# working.net
KiCad netlist of a schematic drawn in EAGLE
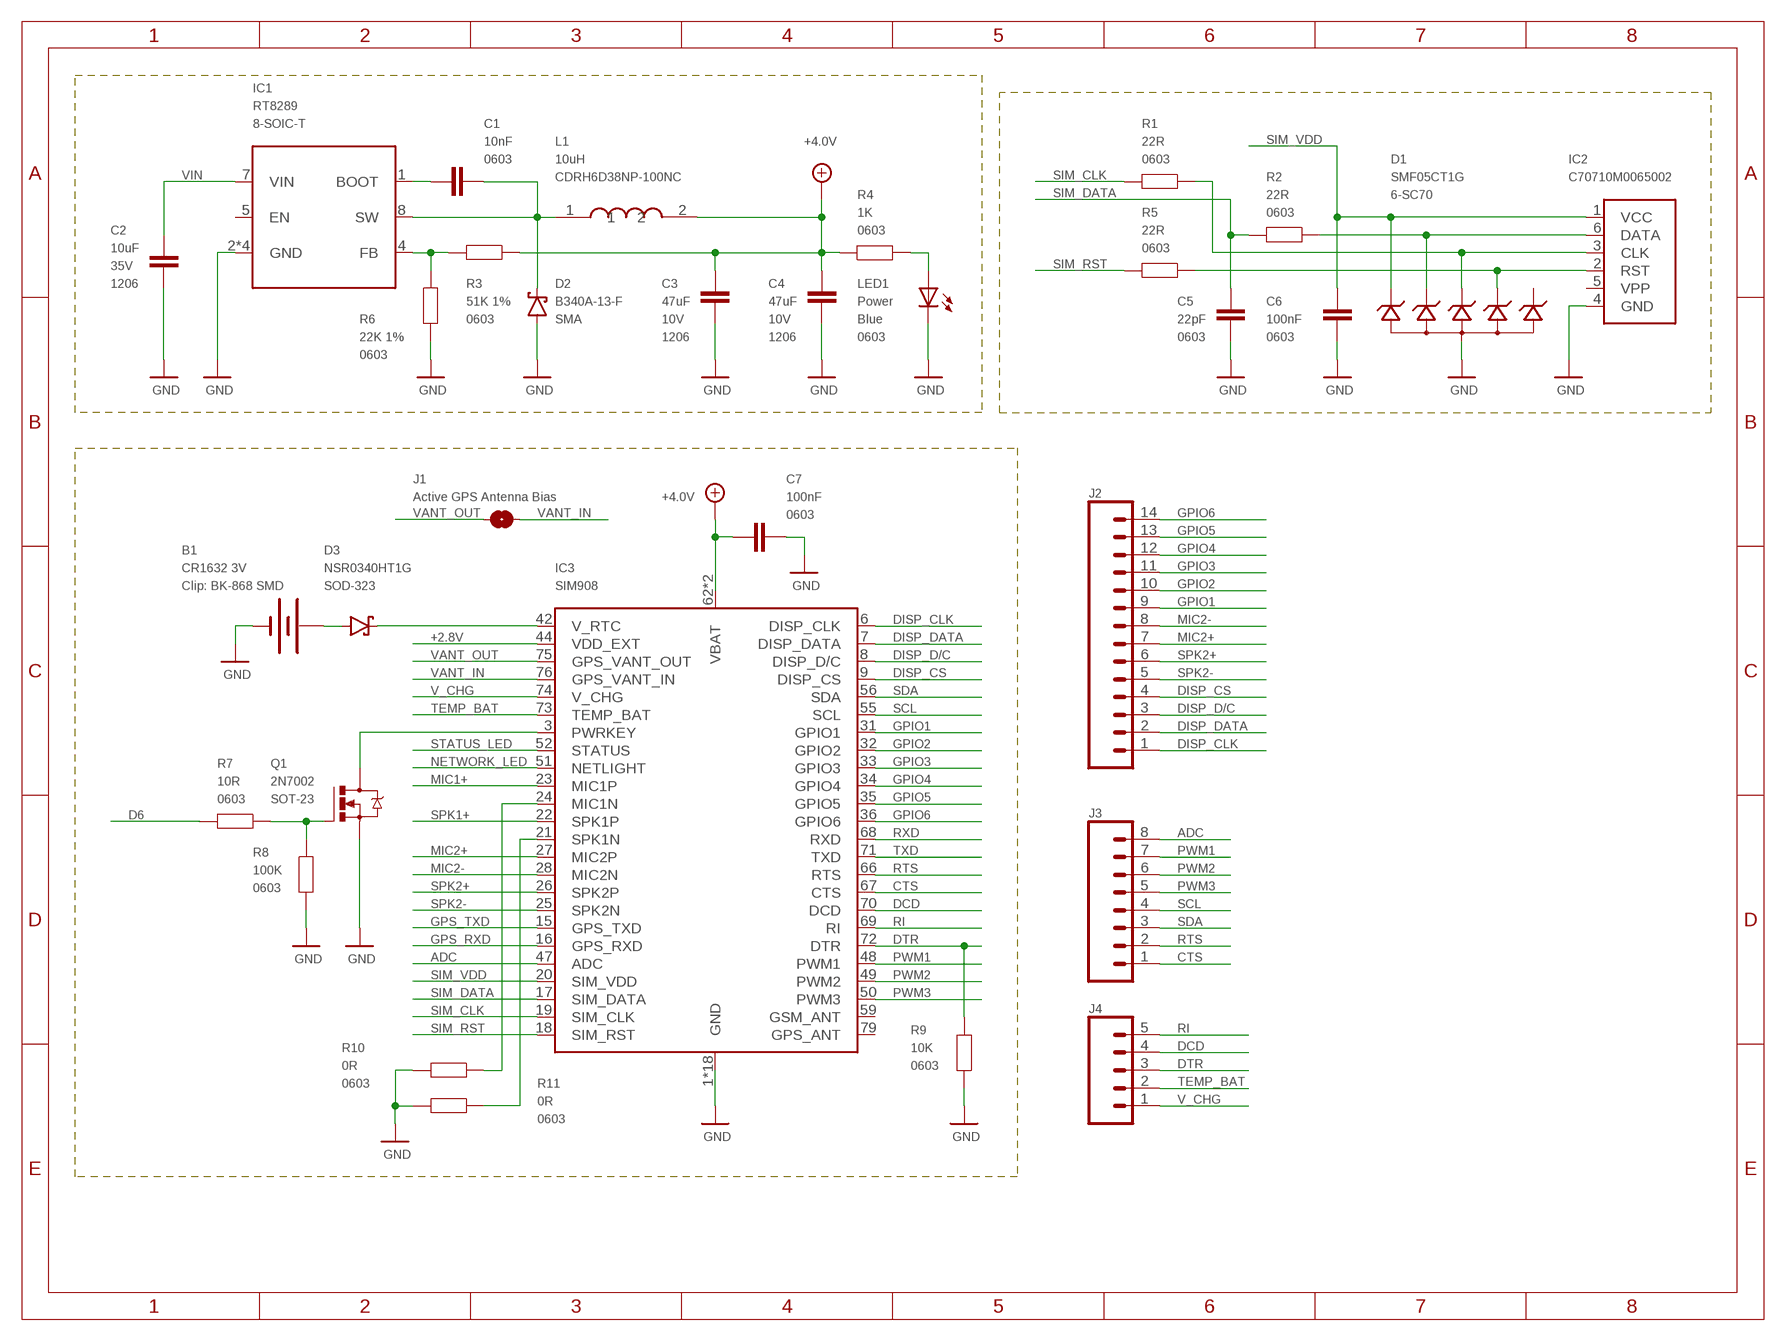
[diagram p0: schematic, sheet 1, part 1 of 2]
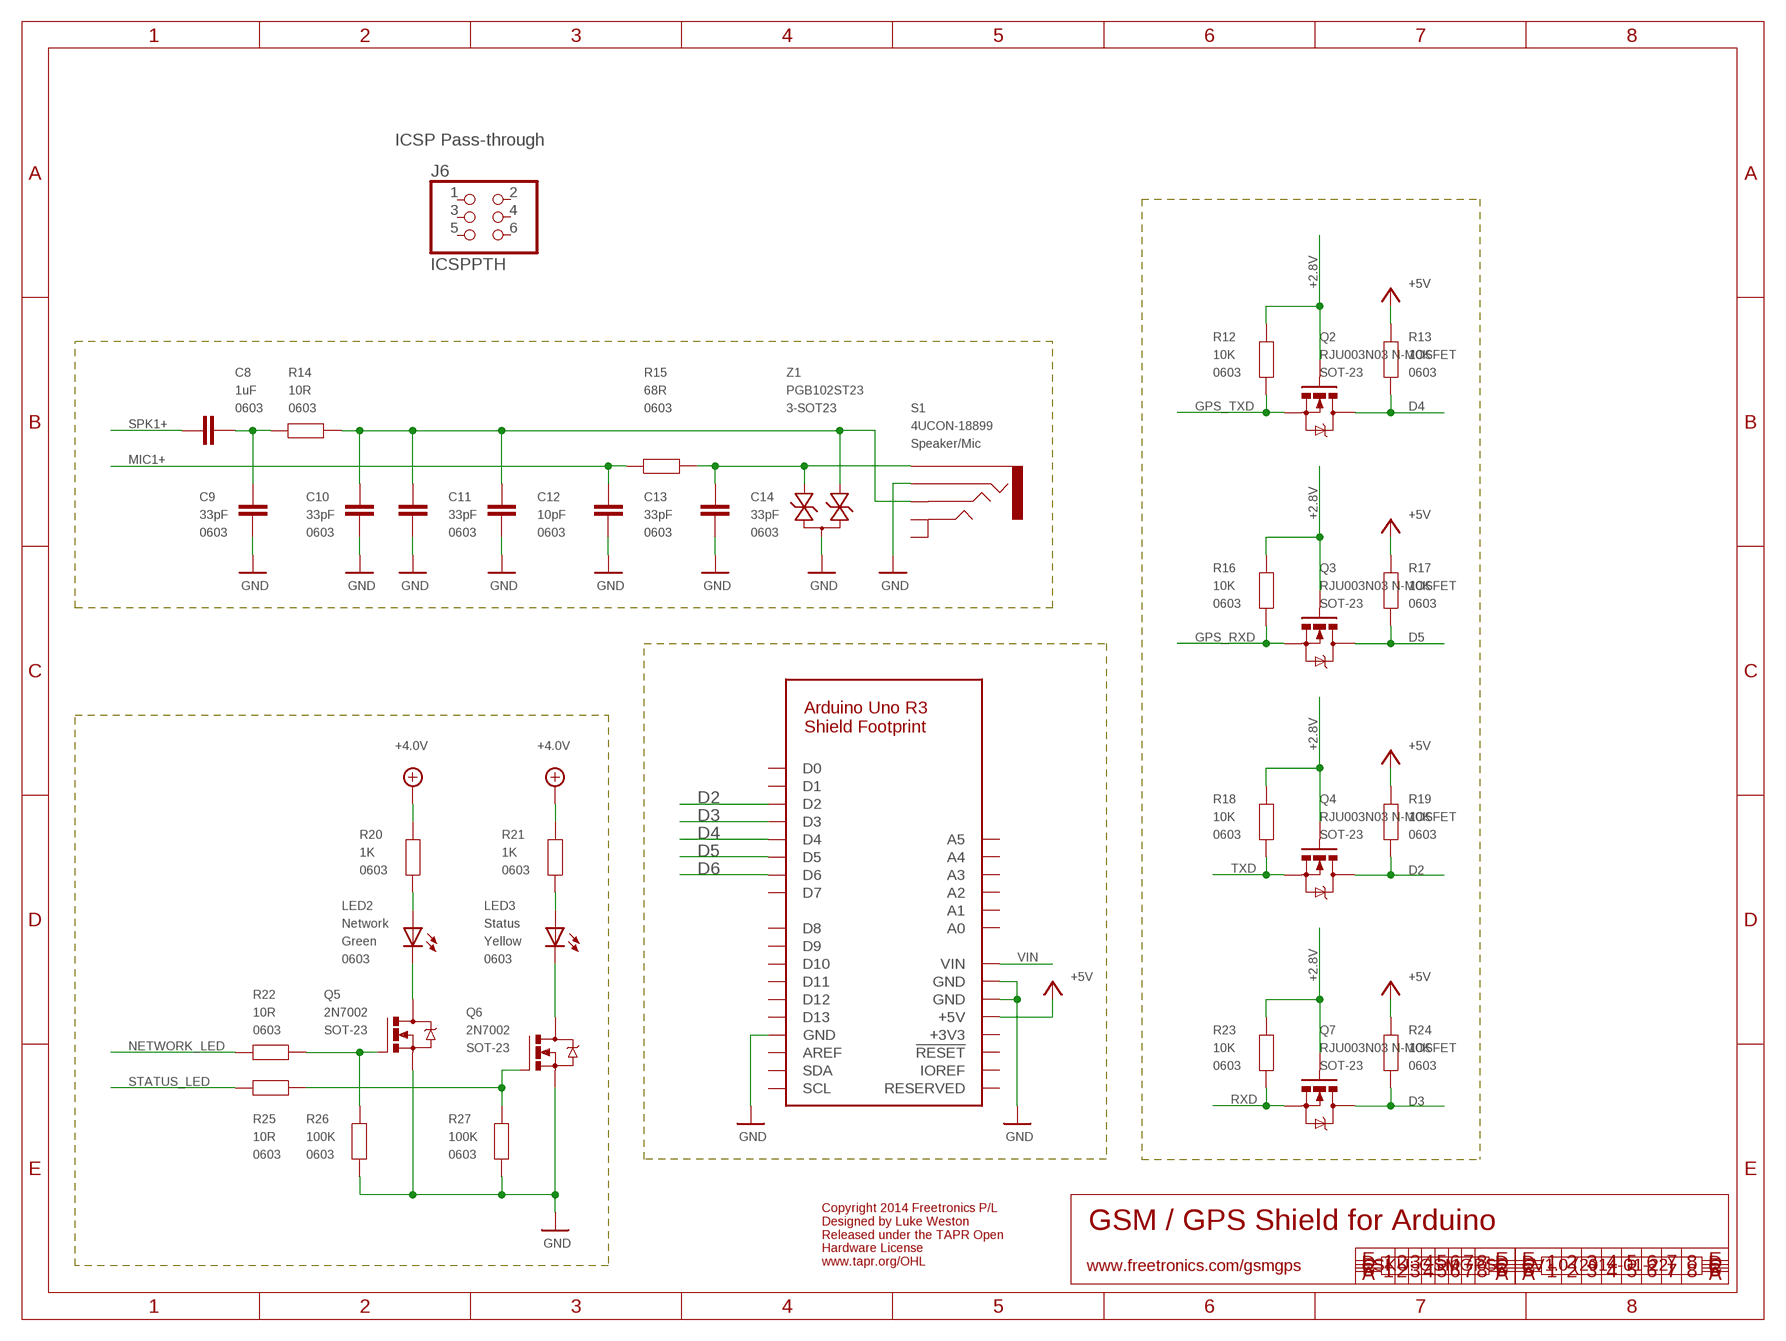
[diagram p1: schematic, sheet 1, part 2 of 2]

(export (version "E")
  (design (tool "Eeschema 10.0.6"))
  (components
    (comp (ref "B1")
      (value "CR1632 3V")
      (footprint "eagle-import:BATCON_16MM")
      (fields (field (name "FOO") "Clip: BK-868 SMD"))
      (libsource (lib "eagle-import") (part "BATTERY"))
    )
    (comp (ref "C1")
      (value "10nF")
      (footprint "eagle-import:0603")
      (fields (field (name "PACKAGE") "0603"))
      (libsource (lib "eagle-import") (part "CAP0603"))
    )
    (comp (ref "C2")
      (value "10uF")
      (footprint "eagle-import:C1206")
      (fields (field (name "PACKAGE") "1206") (field (name "VOLTAGE") "35V"))
      (libsource (lib "eagle-import") (part "C-EUC1206"))
    )
    (comp (ref "C3")
      (value "47uF")
      (footprint "eagle-import:C1206")
      (fields (field (name "PACKAGE") "1206") (field (name "VOLTAGE") "10V"))
      (libsource (lib "eagle-import") (part "C-EUC1206"))
    )
    (comp (ref "C4")
      (value "47uF")
      (footprint "eagle-import:C1206")
      (fields (field (name "PACKAGE") "1206") (field (name "VOLTAGE") "10V"))
      (libsource (lib "eagle-import") (part "C-EUC1206"))
    )
    (comp (ref "C5")
      (value "22pF")
      (footprint "eagle-import:0603")
      (fields (field (name "PACKAGE") "0603"))
      (libsource (lib "eagle-import") (part "CAP0603"))
    )
    (comp (ref "C6")
      (value "100nF")
      (footprint "eagle-import:0603")
      (fields (field (name "PACKAGE") "0603"))
      (libsource (lib "eagle-import") (part "CAP0603"))
    )
    (comp (ref "C7")
      (value "100nF")
      (footprint "eagle-import:0603")
      (fields (field (name "PACKAGE") "0603"))
      (libsource (lib "eagle-import") (part "CAP0603"))
    )
    (comp (ref "C8")
      (value "1uF")
      (footprint "eagle-import:0603")
      (fields (field (name "PACKAGE") "0603"))
      (libsource (lib "eagle-import") (part "CAP0603"))
    )
    (comp (ref "C9")
      (value "33pF")
      (footprint "eagle-import:0603")
      (fields (field (name "PACKAGE") "0603"))
      (libsource (lib "eagle-import") (part "CAP0603"))
    )
    (comp (ref "C10")
      (value "33pF")
      (footprint "eagle-import:0603")
      (fields (field (name "PACKAGE") "0603"))
      (libsource (lib "eagle-import") (part "CAP0603"))
    )
    (comp (ref "C11")
      (value "33pF")
      (footprint "eagle-import:0603")
      (fields (field (name "PACKAGE") "0603"))
      (libsource (lib "eagle-import") (part "CAP0603"))
    )
    (comp (ref "C12")
      (value "10pF")
      (footprint "eagle-import:0603")
      (fields (field (name "PACKAGE") "0603"))
      (libsource (lib "eagle-import") (part "CAP0603"))
    )
    (comp (ref "C13")
      (value "33pF")
      (footprint "eagle-import:0603")
      (fields (field (name "PACKAGE") "0603"))
      (libsource (lib "eagle-import") (part "CAP0603"))
    )
    (comp (ref "C14")
      (value "33pF")
      (footprint "eagle-import:0603")
      (fields (field (name "PACKAGE") "0603"))
      (libsource (lib "eagle-import") (part "CAP0603"))
    )
    (comp (ref "D1")
      (value "SMF05CT1G")
      (footprint "eagle-import:SC70-6")
      (fields (field (name "PACKAGE") "6-SC70"))
      (libsource (lib "eagle-import") (part "SMF05CT1G"))
    )
    (comp (ref "D2")
      (value "B340A-13-F")
      (footprint "eagle-import:SMA")
      (fields (field (name "PACKAGE") "SMA"))
      (libsource (lib "eagle-import") (part "SCHOTTKY-SMA"))
    )
    (comp (ref "D3")
      (value "NSR0340HT1G")
      (footprint "eagle-import:SOD-323")
      (fields (field (name "PACKAGE") "SOD-323"))
      (libsource (lib "eagle-import") (part "SCHOTTKY-SOD323"))
    )
    (comp (ref "IC1")
      (value "RT8289")
      (footprint "eagle-import:SO08T")
      (fields (field (name "PACKAGE") "8-SOIC-T"))
      (libsource (lib "eagle-import") (part "RT8289"))
    )
    (comp (ref "IC2")
      (value "C70710M0065002")
      (footprint "eagle-import:C70710M0065002")
      (libsource (lib "eagle-import") (part "C70710M0065002"))
    )
    (comp (ref "IC3")
      (value "SIM908")
      (footprint "eagle-import:SIM908")
      (libsource (lib "eagle-import") (part "SIM908"))
    )
    (comp (ref "J1")
      (value "Active GPS Antenna Bias")
      (footprint "eagle-import:SJ")
      (libsource (lib "eagle-import") (part "SJ"))
    )
    (comp (ref "J2")
      (value "M14")
      (footprint "eagle-import:1X14")
      (libsource (lib "eagle-import") (part "M14"))
    )
    (comp (ref "J3")
      (value "M08STD")
      (footprint "eagle-import:1X08")
      (libsource (lib "eagle-import") (part "M08STD"))
    )
    (comp (ref "J4")
      (value "M05PTH")
      (footprint "eagle-import:1X05")
      (libsource (lib "eagle-import") (part "M05PTH"))
    )
    (comp (ref "J5")
      (value "ARDUINO-SHIELD_R3_NOISP")
      (footprint "eagle-import:ARDUINO-SHIELD_R3_NOISP")
      (libsource (lib "eagle-import") (part "ARDUINO-SHIELD_R3_NOISP"))
    )
    (comp (ref "J6")
      (value "ICSPPTH")
      (footprint "eagle-import:2X03PTH")
      (libsource (lib "eagle-import") (part "ICSPPTH"))
    )
    (comp (ref "L1")
      (value "10uH")
      (footprint "eagle-import:CDRH")
      (fields (field (name "ID") "CDRH6D38NP-100NC"))
      (libsource (lib "eagle-import") (part "CDRH6D38SMT"))
    )
    (comp (ref "LED1")
      (value "Power")
      (footprint "eagle-import:LED-0603")
      (fields (field (name "COLOR") "Blue") (field (name "PACKAGE") "0603"))
      (libsource (lib "eagle-import") (part "LED0603"))
    )
    (comp (ref "LED2")
      (value "Network")
      (footprint "eagle-import:LED-0603")
      (fields (field (name "COLOR") "Green") (field (name "PACKAGE") "0603"))
      (libsource (lib "eagle-import") (part "LED0603"))
    )
    (comp (ref "LED3")
      (value "Status")
      (footprint "eagle-import:LED-0603")
      (fields (field (name "COLOR") "Yellow") (field (name "PACKAGE") "0603"))
      (libsource (lib "eagle-import") (part "LED0603"))
    )
    (comp (ref "Q1")
      (value "2N7002")
      (footprint "eagle-import:SOT23-3")
      (fields (field (name "PACKAGE") "SOT-23"))
      (libsource (lib "eagle-import") (part "2N7002"))
    )
    (comp (ref "Q2")
      (value "RJU003N03 N-MOSFET")
      (footprint "eagle-import:SOT32-3")
      (fields (field (name "PACKAGE") "SOT-23"))
      (libsource (lib "eagle-import") (part "MOSFET-NSOT-323"))
    )
    (comp (ref "Q3")
      (value "RJU003N03 N-MOSFET")
      (footprint "eagle-import:SOT32-3")
      (fields (field (name "PACKAGE") "SOT-23"))
      (libsource (lib "eagle-import") (part "MOSFET-NSOT-323"))
    )
    (comp (ref "Q4")
      (value "RJU003N03 N-MOSFET")
      (footprint "eagle-import:SOT32-3")
      (fields (field (name "PACKAGE") "SOT-23"))
      (libsource (lib "eagle-import") (part "MOSFET-NSOT-323"))
    )
    (comp (ref "Q5")
      (value "2N7002")
      (footprint "eagle-import:SOT23-3")
      (fields (field (name "PACKAGE") "SOT-23"))
      (libsource (lib "eagle-import") (part "2N7002"))
    )
    (comp (ref "Q6")
      (value "2N7002")
      (footprint "eagle-import:SOT23-3")
      (fields (field (name "PACKAGE") "SOT-23"))
      (libsource (lib "eagle-import") (part "2N7002"))
    )
    (comp (ref "Q7")
      (value "RJU003N03 N-MOSFET")
      (footprint "eagle-import:SOT32-3")
      (fields (field (name "PACKAGE") "SOT-23"))
      (libsource (lib "eagle-import") (part "MOSFET-NSOT-323"))
    )
    (comp (ref "R1")
      (value "22R")
      (footprint "eagle-import:0603")
      (fields (field (name "PACKAGE") "0603"))
      (libsource (lib "eagle-import") (part "RESISTOR0603"))
    )
    (comp (ref "R2")
      (value "22R")
      (footprint "eagle-import:0603")
      (fields (field (name "PACKAGE") "0603"))
      (libsource (lib "eagle-import") (part "RESISTOR0603"))
    )
    (comp (ref "R3")
      (value "51K 1%")
      (footprint "eagle-import:0603")
      (fields (field (name "PACKAGE") "0603"))
      (libsource (lib "eagle-import") (part "RESISTOR0603"))
    )
    (comp (ref "R4")
      (value "1K")
      (footprint "eagle-import:0603")
      (fields (field (name "PACKAGE") "0603"))
      (libsource (lib "eagle-import") (part "RESISTOR0603"))
    )
    (comp (ref "R5")
      (value "22R")
      (footprint "eagle-import:0603")
      (fields (field (name "PACKAGE") "0603"))
      (libsource (lib "eagle-import") (part "RESISTOR0603"))
    )
    (comp (ref "R6")
      (value "22K 1%")
      (footprint "eagle-import:0603")
      (fields (field (name "PACKAGE") "0603"))
      (libsource (lib "eagle-import") (part "RESISTOR0603"))
    )
    (comp (ref "R7")
      (value "10R")
      (footprint "eagle-import:0603")
      (fields (field (name "PACKAGE") "0603"))
      (libsource (lib "eagle-import") (part "RESISTOR0603"))
    )
    (comp (ref "R8")
      (value "100K")
      (footprint "eagle-import:0603")
      (fields (field (name "PACKAGE") "0603"))
      (libsource (lib "eagle-import") (part "RESISTOR0603"))
    )
    (comp (ref "R9")
      (value "10K")
      (footprint "eagle-import:0603")
      (fields (field (name "PACKAGE") "0603"))
      (libsource (lib "eagle-import") (part "RESISTOR0603"))
    )
    (comp (ref "R10")
      (value "0R")
      (footprint "eagle-import:0603")
      (fields (field (name "PACKAGE") "0603"))
      (libsource (lib "eagle-import") (part "RESISTOR0603"))
    )
    (comp (ref "R11")
      (value "0R")
      (footprint "eagle-import:0603")
      (fields (field (name "PACKAGE") "0603"))
      (libsource (lib "eagle-import") (part "RESISTOR0603"))
    )
    (comp (ref "R12")
      (value "10K")
      (footprint "eagle-import:0603")
      (fields (field (name "PACKAGE") "0603"))
      (libsource (lib "eagle-import") (part "RESISTOR0603"))
    )
    (comp (ref "R13")
      (value "10K")
      (footprint "eagle-import:0603")
      (fields (field (name "PACKAGE") "0603"))
      (libsource (lib "eagle-import") (part "RESISTOR0603"))
    )
    (comp (ref "R14")
      (value "10R")
      (footprint "eagle-import:0603")
      (fields (field (name "PACKAGE") "0603"))
      (libsource (lib "eagle-import") (part "RESISTOR0603"))
    )
    (comp (ref "R15")
      (value "68R")
      (footprint "eagle-import:0603")
      (fields (field (name "PACKAGE") "0603"))
      (libsource (lib "eagle-import") (part "RESISTOR0603"))
    )
    (comp (ref "R16")
      (value "10K")
      (footprint "eagle-import:0603")
      (fields (field (name "PACKAGE") "0603"))
      (libsource (lib "eagle-import") (part "RESISTOR0603"))
    )
    (comp (ref "R17")
      (value "10K")
      (footprint "eagle-import:0603")
      (fields (field (name "PACKAGE") "0603"))
      (libsource (lib "eagle-import") (part "RESISTOR0603"))
    )
    (comp (ref "R18")
      (value "10K")
      (footprint "eagle-import:0603")
      (fields (field (name "PACKAGE") "0603"))
      (libsource (lib "eagle-import") (part "RESISTOR0603"))
    )
    (comp (ref "R19")
      (value "10K")
      (footprint "eagle-import:0603")
      (fields (field (name "PACKAGE") "0603"))
      (libsource (lib "eagle-import") (part "RESISTOR0603"))
    )
    (comp (ref "R20")
      (value "1K")
      (footprint "eagle-import:0603")
      (fields (field (name "PACKAGE") "0603"))
      (libsource (lib "eagle-import") (part "RESISTOR0603"))
    )
    (comp (ref "R21")
      (value "1K")
      (footprint "eagle-import:0603")
      (fields (field (name "PACKAGE") "0603"))
      (libsource (lib "eagle-import") (part "RESISTOR0603"))
    )
    (comp (ref "R22")
      (value "10R")
      (footprint "eagle-import:0603")
      (fields (field (name "PACKAGE") "0603"))
      (libsource (lib "eagle-import") (part "RESISTOR0603"))
    )
    (comp (ref "R23")
      (value "10K")
      (footprint "eagle-import:0603")
      (fields (field (name "PACKAGE") "0603"))
      (libsource (lib "eagle-import") (part "RESISTOR0603"))
    )
    (comp (ref "R24")
      (value "10K")
      (footprint "eagle-import:0603")
      (fields (field (name "PACKAGE") "0603"))
      (libsource (lib "eagle-import") (part "RESISTOR0603"))
    )
    (comp (ref "R25")
      (value "10R")
      (footprint "eagle-import:0603")
      (fields (field (name "PACKAGE") "0603"))
      (libsource (lib "eagle-import") (part "RESISTOR0603"))
    )
    (comp (ref "R26")
      (value "100K")
      (footprint "eagle-import:0603")
      (fields (field (name "PACKAGE") "0603"))
      (libsource (lib "eagle-import") (part "RESISTOR0603"))
    )
    (comp (ref "R27")
      (value "100K")
      (footprint "eagle-import:0603")
      (fields (field (name "PACKAGE") "0603"))
      (libsource (lib "eagle-import") (part "RESISTOR0603"))
    )
    (comp (ref "S1")
      (value "4UCON-18899")
      (footprint "eagle-import:4UCON-18899")
      (fields (field (name "FOO") "Speaker/Mic"))
      (libsource (lib "eagle-import") (part "AUDIO-JACK-4POLE"))
    )
    (comp (ref "Z1")
      (value "PGB102ST23")
      (footprint "eagle-import:SOT23-3")
      (fields (field (name "PACKAGE") "3-SOT23"))
      (libsource (lib "eagle-import") (part "PGB102ST23"))
    )
  )
  (nets
    (net (code "1") (name "+4.0V") (class "Default")
      (node (ref "C3") (pin "1") (pinfunction "1_1") (pintype "passive"))
      (node (ref "C4") (pin "1") (pinfunction "1_1") (pintype "passive"))
      (node (ref "C7") (pin "2") (pinfunction "2_2") (pintype "passive"))
      (node (ref "IC3") (pin "62") (pinfunction "VBAT_62") (pintype "bidirectional"))
      (node (ref "IC3") (pin "63") (pinfunction "VBAT_63") (pintype "bidirectional"))
      (node (ref "L1") (pin "2") (pinfunction "2_2") (pintype "bidirectional"))
      (node (ref "R20") (pin "1") (pinfunction "1_1") (pintype "passive"))
      (node (ref "R21") (pin "1") (pinfunction "1_1") (pintype "passive"))
      (node (ref "R3") (pin "1") (pinfunction "1_1") (pintype "passive"))
      (node (ref "R4") (pin "1") (pinfunction "1_1") (pintype "passive"))
    )
    (net (code "2") (name "+5V") (class "Default")
      (node (ref "J5") (pin "+5V") (pinfunction "+5V_+5V") (pintype "power_in"))
      (node (ref "R13") (pin "1") (pinfunction "1_1") (pintype "passive"))
      (node (ref "R17") (pin "1") (pinfunction "1_1") (pintype "passive"))
      (node (ref "R19") (pin "1") (pinfunction "1_1") (pintype "passive"))
      (node (ref "R24") (pin "1") (pinfunction "1_1") (pintype "passive"))
    )
    (net (code "3") (name "/+2.8V") (class "Default")
      (node (ref "IC3") (pin "44") (pinfunction "VDD_EXT_44") (pintype "bidirectional"))
      (node (ref "Q2") (pin "1") (pinfunction "G_1") (pintype "passive"))
      (node (ref "Q3") (pin "1") (pinfunction "G_1") (pintype "passive"))
      (node (ref "Q4") (pin "1") (pinfunction "G_1") (pintype "passive"))
      (node (ref "Q7") (pin "1") (pinfunction "G_1") (pintype "passive"))
      (node (ref "R12") (pin "1") (pinfunction "1_1") (pintype "passive"))
      (node (ref "R16") (pin "1") (pinfunction "1_1") (pintype "passive"))
      (node (ref "R18") (pin "1") (pinfunction "1_1") (pintype "passive"))
      (node (ref "R23") (pin "1") (pinfunction "1_1") (pintype "passive"))
    )
    (net (code "4") (name "/+3V3") (class "Default")
      (node (ref "J5") (pin "3V3") (pinfunction "+3V3_3V3") (pintype "power_in"))
    )
    (net (code "5") (name "/ADC") (class "Default")
      (node (ref "IC3") (pin "47") (pinfunction "ADC_47") (pintype "bidirectional"))
      (node (ref "J3") (pin "8") (pinfunction "8_8") (pintype "passive"))
    )
    (net (code "6") (name "/CTS") (class "Default")
      (node (ref "IC3") (pin "67") (pinfunction "CTS_67") (pintype "bidirectional"))
      (node (ref "J3") (pin "1") (pinfunction "1_1") (pintype "passive"))
    )
    (net (code "7") (name "/D2") (class "Default")
      (node (ref "J5") (pin "D2") (pinfunction "D2_D2") (pintype "bidirectional"))
      (node (ref "Q4") (pin "3") (pinfunction "D_3") (pintype "passive"))
      (node (ref "R19") (pin "2") (pinfunction "2_2") (pintype "passive"))
    )
    (net (code "8") (name "/D3") (class "Default")
      (node (ref "J5") (pin "D3") (pinfunction "D3_D3") (pintype "bidirectional"))
      (node (ref "Q7") (pin "3") (pinfunction "D_3") (pintype "passive"))
      (node (ref "R24") (pin "2") (pinfunction "2_2") (pintype "passive"))
    )
    (net (code "9") (name "/D4") (class "Default")
      (node (ref "J5") (pin "D4") (pinfunction "D4_D4") (pintype "bidirectional"))
      (node (ref "Q2") (pin "3") (pinfunction "D_3") (pintype "passive"))
      (node (ref "R13") (pin "2") (pinfunction "2_2") (pintype "passive"))
    )
    (net (code "10") (name "/D5") (class "Default")
      (node (ref "J5") (pin "D5") (pinfunction "D5_D5") (pintype "bidirectional"))
      (node (ref "Q3") (pin "3") (pinfunction "D_3") (pintype "passive"))
      (node (ref "R17") (pin "2") (pinfunction "2_2") (pintype "passive"))
    )
    (net (code "11") (name "/D6") (class "Default")
      (node (ref "J5") (pin "D6") (pinfunction "D6_D6") (pintype "bidirectional"))
      (node (ref "R7") (pin "2") (pinfunction "2_2") (pintype "passive"))
    )
    (net (code "12") (name "/DCD") (class "Default")
      (node (ref "IC3") (pin "70") (pinfunction "DCD_70") (pintype "bidirectional"))
      (node (ref "J4") (pin "4") (pinfunction "4_4") (pintype "passive"))
    )
    (net (code "13") (name "/DISP_CLK") (class "Default")
      (node (ref "IC3") (pin "6") (pinfunction "DISP_CLK_6") (pintype "bidirectional"))
      (node (ref "J2") (pin "1") (pinfunction "1_1") (pintype "passive"))
    )
    (net (code "14") (name "/DISP_CS") (class "Default")
      (node (ref "IC3") (pin "9") (pinfunction "DISP_CS_9") (pintype "bidirectional"))
      (node (ref "J2") (pin "4") (pinfunction "4_4") (pintype "passive"))
    )
    (net (code "15") (name "/DISP_DATA") (class "Default")
      (node (ref "IC3") (pin "7") (pinfunction "DISP_DATA_7") (pintype "bidirectional"))
      (node (ref "J2") (pin "2") (pinfunction "2_2") (pintype "passive"))
    )
    (net (code "16") (name "/DISP_D{slash}C") (class "Default")
      (node (ref "IC3") (pin "8") (pinfunction "DISP_D/C_8") (pintype "bidirectional"))
      (node (ref "J2") (pin "3") (pinfunction "3_3") (pintype "passive"))
    )
    (net (code "17") (name "/DTR") (class "Default")
      (node (ref "IC3") (pin "72") (pinfunction "DTR_72") (pintype "bidirectional"))
      (node (ref "J4") (pin "3") (pinfunction "3_3") (pintype "passive"))
      (node (ref "R9") (pin "1") (pinfunction "1_1") (pintype "passive"))
    )
    (net (code "18") (name "/GPIO1") (class "Default")
      (node (ref "IC3") (pin "31") (pinfunction "GPIO1_31") (pintype "bidirectional"))
      (node (ref "J2") (pin "9") (pinfunction "9_9") (pintype "passive"))
    )
    (net (code "19") (name "/GPIO2") (class "Default")
      (node (ref "IC3") (pin "32") (pinfunction "GPIO2_32") (pintype "bidirectional"))
      (node (ref "J2") (pin "10") (pinfunction "10_10") (pintype "passive"))
    )
    (net (code "20") (name "/GPIO3") (class "Default")
      (node (ref "IC3") (pin "33") (pinfunction "GPIO3_33") (pintype "bidirectional"))
      (node (ref "J2") (pin "11") (pinfunction "11_11") (pintype "passive"))
    )
    (net (code "21") (name "/GPIO4") (class "Default")
      (node (ref "IC3") (pin "34") (pinfunction "GPIO4_34") (pintype "bidirectional"))
      (node (ref "J2") (pin "12") (pinfunction "12_12") (pintype "passive"))
    )
    (net (code "22") (name "/GPIO5") (class "Default")
      (node (ref "IC3") (pin "35") (pinfunction "GPIO5_35") (pintype "bidirectional"))
      (node (ref "J2") (pin "13") (pinfunction "13_13") (pintype "passive"))
    )
    (net (code "23") (name "/GPIO6") (class "Default")
      (node (ref "IC3") (pin "36") (pinfunction "GPIO6_36") (pintype "bidirectional"))
      (node (ref "J2") (pin "14") (pinfunction "14_14") (pintype "passive"))
    )
    (net (code "24") (name "/GPS_RXD") (class "Default")
      (node (ref "IC3") (pin "16") (pinfunction "GPS_RXD_16") (pintype "bidirectional"))
      (node (ref "Q3") (pin "2") (pinfunction "S_2") (pintype "passive"))
      (node (ref "R16") (pin "2") (pinfunction "2_2") (pintype "passive"))
    )
    (net (code "25") (name "/GPS_TXD") (class "Default")
      (node (ref "IC3") (pin "15") (pinfunction "GPS_TXD_15") (pintype "bidirectional"))
      (node (ref "Q2") (pin "2") (pinfunction "S_2") (pintype "passive"))
      (node (ref "R12") (pin "2") (pinfunction "2_2") (pintype "passive"))
    )
    (net (code "26") (name "/MIC1+") (class "Default")
      (node (ref "C13") (pin "2") (pinfunction "2_2") (pintype "passive"))
      (node (ref "IC3") (pin "23") (pinfunction "MIC1P_23") (pintype "bidirectional"))
      (node (ref "R15") (pin "1") (pinfunction "1_1") (pintype "passive"))
    )
    (net (code "27") (name "/MIC2+") (class "Default")
      (node (ref "IC3") (pin "27") (pinfunction "MIC2P_27") (pintype "bidirectional"))
      (node (ref "J2") (pin "7") (pinfunction "7_7") (pintype "passive"))
    )
    (net (code "28") (name "/MIC2-") (class "Default")
      (node (ref "IC3") (pin "28") (pinfunction "MIC2N_28") (pintype "bidirectional"))
      (node (ref "J2") (pin "8") (pinfunction "8_8") (pintype "passive"))
    )
    (net (code "29") (name "/NETWORK_LED") (class "Default")
      (node (ref "IC3") (pin "51") (pinfunction "NETLIGHT_51") (pintype "bidirectional"))
      (node (ref "R22") (pin "2") (pinfunction "2_2") (pintype "passive"))
    )
    (net (code "30") (name "/PWM1") (class "Default")
      (node (ref "IC3") (pin "48") (pinfunction "PWM1_48") (pintype "bidirectional"))
      (node (ref "J3") (pin "7") (pinfunction "7_7") (pintype "passive"))
    )
    (net (code "31") (name "/PWM2") (class "Default")
      (node (ref "IC3") (pin "49") (pinfunction "PWM2_49") (pintype "bidirectional"))
      (node (ref "J3") (pin "6") (pinfunction "6_6") (pintype "passive"))
    )
    (net (code "32") (name "/PWM3") (class "Default")
      (node (ref "IC3") (pin "50") (pinfunction "PWM3_50") (pintype "bidirectional"))
      (node (ref "J3") (pin "5") (pinfunction "5_5") (pintype "passive"))
    )
    (net (code "33") (name "/RI") (class "Default")
      (node (ref "IC3") (pin "69") (pinfunction "RI_69") (pintype "bidirectional"))
      (node (ref "J4") (pin "5") (pinfunction "5_5") (pintype "passive"))
    )
    (net (code "34") (name "/RTS") (class "Default")
      (node (ref "IC3") (pin "66") (pinfunction "RTS_66") (pintype "bidirectional"))
      (node (ref "J3") (pin "2") (pinfunction "2_2") (pintype "passive"))
    )
    (net (code "35") (name "/RXD") (class "Default")
      (node (ref "IC3") (pin "68") (pinfunction "RXD_68") (pintype "bidirectional"))
      (node (ref "Q7") (pin "2") (pinfunction "S_2") (pintype "passive"))
      (node (ref "R23") (pin "2") (pinfunction "2_2") (pintype "passive"))
    )
    (net (code "36") (name "/SCL") (class "Default")
      (node (ref "IC3") (pin "55") (pinfunction "SCL_55") (pintype "bidirectional"))
      (node (ref "J3") (pin "4") (pinfunction "4_4") (pintype "passive"))
    )
    (net (code "37") (name "/SDA") (class "Default")
      (node (ref "IC3") (pin "56") (pinfunction "SDA_56") (pintype "bidirectional"))
      (node (ref "J3") (pin "3") (pinfunction "3_3") (pintype "passive"))
    )
    (net (code "38") (name "/SIM_CLK") (class "Default")
      (node (ref "IC3") (pin "19") (pinfunction "SIM_CLK_19") (pintype "bidirectional"))
      (node (ref "R1") (pin "2") (pinfunction "2_2") (pintype "passive"))
    )
    (net (code "39") (name "/SIM_DATA") (class "Default")
      (node (ref "C5") (pin "2") (pinfunction "2_2") (pintype "passive"))
      (node (ref "IC3") (pin "17") (pinfunction "SIM_DATA_17") (pintype "bidirectional"))
      (node (ref "R2") (pin "2") (pinfunction "2_2") (pintype "passive"))
    )
    (net (code "40") (name "/SIM_RST") (class "Default")
      (node (ref "IC3") (pin "18") (pinfunction "SIM_RST_18") (pintype "bidirectional"))
      (node (ref "R5") (pin "2") (pinfunction "2_2") (pintype "passive"))
    )
    (net (code "41") (name "/SIM_VDD") (class "Default")
      (node (ref "C6") (pin "2") (pinfunction "2_2") (pintype "passive"))
      (node (ref "D1") (pin "1") (pinfunction "K1_1") (pintype "bidirectional"))
      (node (ref "IC2") (pin "1") (pinfunction "VCC_1") (pintype "bidirectional"))
      (node (ref "IC3") (pin "20") (pinfunction "SIM_VDD_20") (pintype "bidirectional"))
    )
    (net (code "42") (name "/SPK1+") (class "Default")
      (node (ref "C8") (pin "2") (pinfunction "2_2") (pintype "passive"))
      (node (ref "IC3") (pin "22") (pinfunction "SPK1P_22") (pintype "bidirectional"))
    )
    (net (code "43") (name "/SPK2+") (class "Default")
      (node (ref "IC3") (pin "26") (pinfunction "SPK2P_26") (pintype "bidirectional"))
      (node (ref "J2") (pin "6") (pinfunction "6_6") (pintype "passive"))
    )
    (net (code "44") (name "/SPK2-") (class "Default")
      (node (ref "IC3") (pin "25") (pinfunction "SPK2N_25") (pintype "bidirectional"))
      (node (ref "J2") (pin "5") (pinfunction "5_5") (pintype "passive"))
    )
    (net (code "45") (name "/STATUS_LED") (class "Default")
      (node (ref "IC3") (pin "52") (pinfunction "STATUS_52") (pintype "bidirectional"))
      (node (ref "R25") (pin "2") (pinfunction "2_2") (pintype "passive"))
    )
    (net (code "46") (name "/TEMP_BAT") (class "Default")
      (node (ref "IC3") (pin "73") (pinfunction "TEMP_BAT_73") (pintype "bidirectional"))
      (node (ref "J4") (pin "2") (pinfunction "2_2") (pintype "passive"))
    )
    (net (code "47") (name "/TXD") (class "Default")
      (node (ref "IC3") (pin "71") (pinfunction "TXD_71") (pintype "bidirectional"))
      (node (ref "Q4") (pin "2") (pinfunction "S_2") (pintype "passive"))
      (node (ref "R18") (pin "2") (pinfunction "2_2") (pintype "passive"))
    )
    (net (code "48") (name "/VANT_IN") (class "Default")
      (node (ref "IC3") (pin "76") (pinfunction "GPS_VANT_IN_76") (pintype "bidirectional"))
      (node (ref "J1") (pin "2") (pinfunction "2_2") (pintype "passive"))
    )
    (net (code "49") (name "/VANT_OUT") (class "Default")
      (node (ref "IC3") (pin "75") (pinfunction "GPS_VANT_OUT_75") (pintype "bidirectional"))
      (node (ref "J1") (pin "1") (pinfunction "1_1") (pintype "passive"))
    )
    (net (code "50") (name "/VIN") (class "Default")
      (node (ref "C2") (pin "1") (pinfunction "1_1") (pintype "passive"))
      (node (ref "IC1") (pin "7") (pinfunction "VIN_7") (pintype "bidirectional"))
      (node (ref "J5") (pin "VIN") (pinfunction "VIN_VIN") (pintype "power_in"))
    )
    (net (code "51") (name "/V_CHG") (class "Default")
      (node (ref "IC3") (pin "74") (pinfunction "V_CHG_74") (pintype "bidirectional"))
      (node (ref "J4") (pin "1") (pinfunction "1_1") (pintype "passive"))
    )
    (net (code "52") (name "GND") (class "Default")
      (node (ref "B1") (pin "GND") (pinfunction "-_GND") (pintype "power_in"))
      (node (ref "C10") (pin "1") (pinfunction "1_1") (pintype "passive"))
      (node (ref "C11") (pin "1") (pinfunction "1_1") (pintype "passive"))
      (node (ref "C12") (pin "1") (pinfunction "1_1") (pintype "passive"))
      (node (ref "C13") (pin "1") (pinfunction "1_1") (pintype "passive"))
      (node (ref "C14") (pin "1") (pinfunction "1_1") (pintype "passive"))
      (node (ref "C2") (pin "2") (pinfunction "2_2") (pintype "passive"))
      (node (ref "C3") (pin "2") (pinfunction "2_2") (pintype "passive"))
      (node (ref "C4") (pin "2") (pinfunction "2_2") (pintype "passive"))
      (node (ref "C5") (pin "1") (pinfunction "1_1") (pintype "passive"))
      (node (ref "C6") (pin "1") (pinfunction "1_1") (pintype "passive"))
      (node (ref "C7") (pin "1") (pinfunction "1_1") (pintype "passive"))
      (node (ref "C9") (pin "1") (pinfunction "1_1") (pintype "passive"))
      (node (ref "D1") (pin "2") (pinfunction "A2_2") (pintype "bidirectional"))
      (node (ref "D2") (pin "A") (pinfunction "A_A") (pintype "passive"))
      (node (ref "IC1") (pin "2") (pinfunction "GND_2") (pintype "bidirectional"))
      (node (ref "IC1") (pin "3") (pinfunction "GND_3") (pintype "bidirectional"))
      (node (ref "IC1") (pin "6") (pinfunction "GND_6") (pintype "bidirectional"))
      (node (ref "IC1") (pin "PAD") (pinfunction "GND_PAD") (pintype "bidirectional"))
      (node (ref "IC2") (pin "4") (pinfunction "GND_4") (pintype "bidirectional"))
      (node (ref "IC3") (pin "1") (pinfunction "GND_1") (pintype "bidirectional"))
      (node (ref "IC3") (pin "10") (pinfunction "GND_10") (pintype "bidirectional"))
      (node (ref "IC3") (pin "14") (pinfunction "GND_14") (pintype "bidirectional"))
      (node (ref "IC3") (pin "2") (pinfunction "GND_2") (pintype "bidirectional"))
      (node (ref "IC3") (pin "37") (pinfunction "GND_37") (pintype "bidirectional"))
      (node (ref "IC3") (pin "40") (pinfunction "GND_40") (pintype "bidirectional"))
      (node (ref "IC3") (pin "41") (pinfunction "GND_41") (pintype "bidirectional"))
      (node (ref "IC3") (pin "43") (pinfunction "GND_43") (pintype "bidirectional"))
      (node (ref "IC3") (pin "5") (pinfunction "GND_5") (pintype "bidirectional"))
      (node (ref "IC3") (pin "57") (pinfunction "GND_57") (pintype "bidirectional"))
      (node (ref "IC3") (pin "58") (pinfunction "GND_58") (pintype "bidirectional"))
      (node (ref "IC3") (pin "60") (pinfunction "GND_60") (pintype "bidirectional"))
      (node (ref "IC3") (pin "61") (pinfunction "GND_61") (pintype "bidirectional"))
      (node (ref "IC3") (pin "64") (pinfunction "GND_64") (pintype "bidirectional"))
      (node (ref "IC3") (pin "65") (pinfunction "GND_65") (pintype "bidirectional"))
      (node (ref "IC3") (pin "77") (pinfunction "GND_77") (pintype "bidirectional"))
      (node (ref "IC3") (pin "78") (pinfunction "GND_78") (pintype "bidirectional"))
      (node (ref "IC3") (pin "80") (pinfunction "GND_80") (pintype "bidirectional"))
      (node (ref "J5") (pin "GND") (pinfunction "GND_GND") (pintype "power_in"))
      (node (ref "J5") (pin "GND@0") (pinfunction "GND_GND@0") (pintype "power_in"))
      (node (ref "J5") (pin "GND@1") (pinfunction "GND_GND@1") (pintype "power_in"))
      (node (ref "LED1") (pin "C") (pinfunction "C_C") (pintype "passive"))
      (node (ref "Q1") (pin "2") (pinfunction "S_2") (pintype "passive"))
      (node (ref "Q5") (pin "2") (pinfunction "S_2") (pintype "passive"))
      (node (ref "Q6") (pin "2") (pinfunction "S_2") (pintype "passive"))
      (node (ref "R10") (pin "2") (pinfunction "2_2") (pintype "passive"))
      (node (ref "R11") (pin "2") (pinfunction "2_2") (pintype "passive"))
      (node (ref "R26") (pin "1") (pinfunction "1_1") (pintype "passive"))
      (node (ref "R27") (pin "1") (pinfunction "1_1") (pintype "passive"))
      (node (ref "R6") (pin "1") (pinfunction "1_1") (pintype "passive"))
      (node (ref "R8") (pin "1") (pinfunction "1_1") (pintype "passive"))
      (node (ref "R9") (pin "2") (pinfunction "2_2") (pintype "passive"))
      (node (ref "S1") (pin "4") (pinfunction "4_4") (pintype "bidirectional"))
      (node (ref "Z1") (pin "3") (pinfunction "P$3_3") (pintype "bidirectional"))
    )
    (net (code "53") (name "Net-(B1-+)") (class "Default")
      (node (ref "B1") (pin "PWR@1") (pinfunction "+_PWR@1") (pintype "power_in"))
      (node (ref "D3") (pin "A") (pinfunction "A_A") (pintype "passive"))
    )
    (net (code "54") (name "Net-(C8-Pad1)") (class "Default")
      (node (ref "C8") (pin "1") (pinfunction "1_1") (pintype "passive"))
      (node (ref "C9") (pin "2") (pinfunction "2_2") (pintype "passive"))
      (node (ref "R14") (pin "1") (pinfunction "1_1") (pintype "passive"))
    )
    (net (code "55") (name "Net-(D1-K3)") (class "Default")
      (node (ref "D1") (pin "3") (pinfunction "K3_3") (pintype "bidirectional"))
      (node (ref "IC2") (pin "6") (pinfunction "DATA_6") (pintype "bidirectional"))
      (node (ref "R2") (pin "1") (pinfunction "1_1") (pintype "passive"))
    )
    (net (code "56") (name "Net-(D1-K4)") (class "Default")
      (node (ref "D1") (pin "4") (pinfunction "K4_4") (pintype "bidirectional"))
      (node (ref "IC2") (pin "3") (pinfunction "CLK_3") (pintype "bidirectional"))
      (node (ref "R1") (pin "1") (pinfunction "1_1") (pintype "passive"))
    )
    (net (code "57") (name "Net-(D1-K5)") (class "Default")
      (node (ref "D1") (pin "5") (pinfunction "K5_5") (pintype "bidirectional"))
      (node (ref "IC2") (pin "2") (pinfunction "RST_2") (pintype "bidirectional"))
      (node (ref "R5") (pin "1") (pinfunction "1_1") (pintype "passive"))
    )
    (net (code "58") (name "Net-(IC1-BOOT)") (class "Default")
      (node (ref "C1") (pin "2") (pinfunction "2_2") (pintype "passive"))
      (node (ref "IC1") (pin "1") (pinfunction "BOOT_1") (pintype "bidirectional"))
    )
    (net (code "59") (name "Net-(IC1-FB)") (class "Default")
      (node (ref "IC1") (pin "4") (pinfunction "FB_4") (pintype "bidirectional"))
      (node (ref "R3") (pin "2") (pinfunction "2_2") (pintype "passive"))
      (node (ref "R6") (pin "2") (pinfunction "2_2") (pintype "passive"))
    )
    (net (code "60") (name "Net-(IC1-SW)") (class "Default")
      (node (ref "C1") (pin "1") (pinfunction "1_1") (pintype "passive"))
      (node (ref "D2") (pin "K") (pinfunction "K_K") (pintype "passive"))
      (node (ref "IC1") (pin "8") (pinfunction "SW_8") (pintype "bidirectional"))
      (node (ref "L1") (pin "1") (pinfunction "1_1") (pintype "bidirectional"))
    )
    (net (code "61") (name "Net-(IC3-MIC1N)") (class "Default")
      (node (ref "IC3") (pin "24") (pinfunction "MIC1N_24") (pintype "bidirectional"))
      (node (ref "R10") (pin "1") (pinfunction "1_1") (pintype "passive"))
    )
    (net (code "62") (name "Net-(IC3-PWRKEY)") (class "Default")
      (node (ref "IC3") (pin "3") (pinfunction "PWRKEY_3") (pintype "bidirectional"))
      (node (ref "Q1") (pin "3") (pinfunction "D_3") (pintype "passive"))
    )
    (net (code "63") (name "Net-(IC3-SPK1N)") (class "Default")
      (node (ref "IC3") (pin "21") (pinfunction "SPK1N_21") (pintype "bidirectional"))
      (node (ref "R11") (pin "1") (pinfunction "1_1") (pintype "passive"))
    )
    (net (code "64") (name "Net-(IC3-V_RTC)") (class "Default")
      (node (ref "D3") (pin "K") (pinfunction "K_K") (pintype "passive"))
      (node (ref "IC3") (pin "42") (pinfunction "V_RTC_42") (pintype "bidirectional"))
    )
    (net (code "65") (name "Net-(LED1-PadA)") (class "Default")
      (node (ref "LED1") (pin "A") (pinfunction "A_A") (pintype "passive"))
      (node (ref "R4") (pin "2") (pinfunction "2_2") (pintype "passive"))
    )
    (net (code "66") (name "Net-(LED2-PadA)") (class "Default")
      (node (ref "LED2") (pin "A") (pinfunction "A_A") (pintype "passive"))
      (node (ref "R20") (pin "2") (pinfunction "2_2") (pintype "passive"))
    )
    (net (code "67") (name "Net-(LED3-PadA)") (class "Default")
      (node (ref "LED3") (pin "A") (pinfunction "A_A") (pintype "passive"))
      (node (ref "R21") (pin "2") (pinfunction "2_2") (pintype "passive"))
    )
    (net (code "68") (name "Net-(Q1-G)") (class "Default")
      (node (ref "Q1") (pin "1") (pinfunction "G_1") (pintype "passive"))
      (node (ref "R7") (pin "1") (pinfunction "1_1") (pintype "passive"))
      (node (ref "R8") (pin "2") (pinfunction "2_2") (pintype "passive"))
    )
    (net (code "69") (name "Net-(Q5-D)") (class "Default")
      (node (ref "LED2") (pin "C") (pinfunction "C_C") (pintype "passive"))
      (node (ref "Q5") (pin "3") (pinfunction "D_3") (pintype "passive"))
    )
    (net (code "70") (name "Net-(Q5-G)") (class "Default")
      (node (ref "Q5") (pin "1") (pinfunction "G_1") (pintype "passive"))
      (node (ref "R22") (pin "1") (pinfunction "1_1") (pintype "passive"))
      (node (ref "R26") (pin "2") (pinfunction "2_2") (pintype "passive"))
    )
    (net (code "71") (name "Net-(Q6-D)") (class "Default")
      (node (ref "LED3") (pin "C") (pinfunction "C_C") (pintype "passive"))
      (node (ref "Q6") (pin "3") (pinfunction "D_3") (pintype "passive"))
    )
    (net (code "72") (name "Net-(Q6-G)") (class "Default")
      (node (ref "Q6") (pin "1") (pinfunction "G_1") (pintype "passive"))
      (node (ref "R25") (pin "1") (pinfunction "1_1") (pintype "passive"))
      (node (ref "R27") (pin "2") (pinfunction "2_2") (pintype "passive"))
    )
    (net (code "73") (name "Net-(Z1-P$1)") (class "Default")
      (node (ref "C10") (pin "2") (pinfunction "2_2") (pintype "passive"))
      (node (ref "C11") (pin "2") (pinfunction "2_2") (pintype "passive"))
      (node (ref "C12") (pin "2") (pinfunction "2_2") (pintype "passive"))
      (node (ref "R14") (pin "2") (pinfunction "2_2") (pintype "passive"))
      (node (ref "S1") (pin "3") (pinfunction "3_3") (pintype "bidirectional"))
      (node (ref "Z1") (pin "1") (pinfunction "P$1_1") (pintype "bidirectional"))
    )
    (net (code "74") (name "Net-(Z1-P$2)") (class "Default")
      (node (ref "C14") (pin "2") (pinfunction "2_2") (pintype "passive"))
      (node (ref "R15") (pin "2") (pinfunction "2_2") (pintype "passive"))
      (node (ref "S1") (pin "1") (pinfunction "1_1") (pintype "bidirectional"))
      (node (ref "Z1") (pin "2") (pinfunction "P$2_2") (pintype "bidirectional"))
    )
    (net (code "75") (name "unconnected-(D1-K6-Pad6)") (class "Default")
      (node (ref "D1") (pin "6") (pinfunction "K6_6") (pintype "bidirectional"))
    )
    (net (code "76") (name "unconnected-(IC1-EN-Pad5)") (class "Default")
      (node (ref "IC1") (pin "5") (pinfunction "EN_5") (pintype "bidirectional"))
    )
    (net (code "77") (name "unconnected-(IC2-VPP-Pad5)") (class "Default")
      (node (ref "IC2") (pin "5") (pinfunction "VPP_5") (pintype "bidirectional"))
    )
    (net (code "78") (name "unconnected-(IC3-GPS_ANT-Pad79)") (class "Default")
      (node (ref "IC3") (pin "79") (pinfunction "GPS_ANT_79") (pintype "bidirectional"))
    )
    (net (code "79") (name "unconnected-(IC3-GSM_ANT-Pad59)") (class "Default")
      (node (ref "IC3") (pin "59") (pinfunction "GSM_ANT_59") (pintype "bidirectional"))
    )
    (net (code "80") (name "unconnected-(J5-PadA0)") (class "Default")
      (node (ref "J5") (pin "A0") (pinfunction "A0_A0") (pintype "bidirectional"))
    )
    (net (code "81") (name "unconnected-(J5-PadA1)") (class "Default")
      (node (ref "J5") (pin "A1") (pinfunction "A1_A1") (pintype "bidirectional"))
    )
    (net (code "82") (name "unconnected-(J5-PadA2)") (class "Default")
      (node (ref "J5") (pin "A2") (pinfunction "A2_A2") (pintype "bidirectional"))
    )
    (net (code "83") (name "unconnected-(J5-PadA3)") (class "Default")
      (node (ref "J5") (pin "A3") (pinfunction "A3_A3") (pintype "bidirectional"))
    )
    (net (code "84") (name "unconnected-(J5-PadA4)") (class "Default")
      (node (ref "J5") (pin "A4") (pinfunction "A4_A4") (pintype "bidirectional"))
    )
    (net (code "85") (name "unconnected-(J5-PadA5)") (class "Default")
      (node (ref "J5") (pin "A5") (pinfunction "A5_A5") (pintype "bidirectional"))
    )
    (net (code "86") (name "unconnected-(J5-PadAREF)") (class "Default")
      (node (ref "J5") (pin "AREF") (pinfunction "AREF_AREF") (pintype "bidirectional"))
    )
    (net (code "87") (name "unconnected-(J5-PadD0)") (class "Default")
      (node (ref "J5") (pin "D0") (pinfunction "D0_D0") (pintype "bidirectional"))
    )
    (net (code "88") (name "unconnected-(J5-PadD1)") (class "Default")
      (node (ref "J5") (pin "D1") (pinfunction "D1_D1") (pintype "bidirectional"))
    )
    (net (code "89") (name "unconnected-(J5-PadD7)") (class "Default")
      (node (ref "J5") (pin "D7") (pinfunction "D7_D7") (pintype "bidirectional"))
    )
    (net (code "90") (name "unconnected-(J5-PadD8)") (class "Default")
      (node (ref "J5") (pin "D8") (pinfunction "D8_D8") (pintype "bidirectional"))
    )
    (net (code "91") (name "unconnected-(J5-PadD9)") (class "Default")
      (node (ref "J5") (pin "D9") (pinfunction "D9_D9") (pintype "bidirectional"))
    )
    (net (code "92") (name "unconnected-(J5-PadD10)") (class "Default")
      (node (ref "J5") (pin "D10") (pinfunction "D10_D10") (pintype "bidirectional"))
    )
    (net (code "93") (name "unconnected-(J5-PadD11)") (class "Default")
      (node (ref "J5") (pin "D11") (pinfunction "D11_D11") (pintype "bidirectional"))
    )
    (net (code "94") (name "unconnected-(J5-PadD12)") (class "Default")
      (node (ref "J5") (pin "D12") (pinfunction "D12_D12") (pintype "bidirectional"))
    )
    (net (code "95") (name "unconnected-(J5-PadD13)") (class "Default")
      (node (ref "J5") (pin "D13") (pinfunction "D13_D13") (pintype "bidirectional"))
    )
    (net (code "96") (name "unconnected-(J5-PadIOREF)") (class "Default")
      (node (ref "J5") (pin "IOREF") (pinfunction "IOREF_IOREF") (pintype "output"))
    )
    (net (code "97") (name "unconnected-(J5-PadRESERVED)") (class "Default")
      (node (ref "J5") (pin "RESERVED") (pinfunction "RESERVED_RESERVED") (pintype "no_connect"))
    )
    (net (code "98") (name "unconnected-(J5-PadSCL)") (class "Default")
      (node (ref "J5") (pin "SCL") (pinfunction "SCL_SCL") (pintype "bidirectional"))
    )
    (net (code "99") (name "unconnected-(J5-PadSDA)") (class "Default")
      (node (ref "J5") (pin "SDA") (pinfunction "SDA_SDA") (pintype "bidirectional"))
    )
    (net (code "100") (name "unconnected-(J5-~{RESET}-Pad!RESET)") (class "Default")
      (node (ref "J5") (pin "!RESET") (pinfunction "~{RESET}_!RESET") (pintype "bidirectional"))
    )
    (net (code "101") (name "unconnected-(J6-Pad1)") (class "Default")
      (node (ref "J6") (pin "1") (pinfunction "1_1") (pintype "passive"))
    )
    (net (code "102") (name "unconnected-(J6-Pad2)") (class "Default")
      (node (ref "J6") (pin "2") (pinfunction "2_2") (pintype "passive"))
    )
    (net (code "103") (name "unconnected-(J6-Pad3)") (class "Default")
      (node (ref "J6") (pin "3") (pinfunction "3_3") (pintype "passive"))
    )
    (net (code "104") (name "unconnected-(J6-Pad4)") (class "Default")
      (node (ref "J6") (pin "4") (pinfunction "4_4") (pintype "passive"))
    )
    (net (code "105") (name "unconnected-(J6-Pad5)") (class "Default")
      (node (ref "J6") (pin "5") (pinfunction "5_5") (pintype "passive"))
    )
    (net (code "106") (name "unconnected-(J6-Pad6)") (class "Default")
      (node (ref "J6") (pin "6") (pinfunction "6_6") (pintype "passive"))
    )
    (net (code "107") (name "unconnected-(S1-Pad2A)") (class "Default")
      (node (ref "S1") (pin "2A") (pinfunction "2A_2A") (pintype "bidirectional"))
    )
    (net (code "108") (name "unconnected-(S1-Pad2B)") (class "Default")
      (node (ref "S1") (pin "2B") (pinfunction "2B_2B") (pintype "bidirectional"))
    )
  )
)
